# Bluepill.net
KiCad netlist of a schematic drawn in Altium Designer
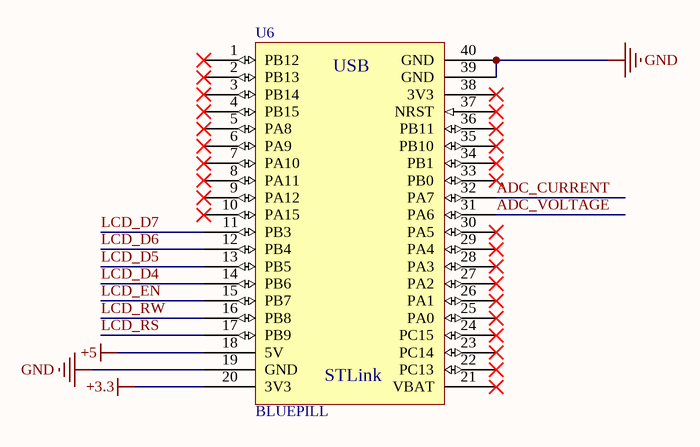
[diagram p0: Bluepill.SchDoc]

(export (version "E")
  (design (tool "Eeschema 10.0.6"))
  (components
    (comp (ref "U6")
      (value "BLUEPILL")
      (footprint "BLUEPILL")
      (description "Development board STM32F103C8T6")
      (libsource (lib "Giang's Libs") (part "BLUEPILL"))
    )
  )
  (nets
    (net (code "1") (name "+3.3") (class "Default")
      (node (ref "U6") (pin "20") (pinfunction "3V3_20") (pintype "power_in"))
    )
    (net (code "2") (name "+5") (class "Default")
      (node (ref "U6") (pin "18") (pinfunction "5V_18") (pintype "power_in"))
    )
    (net (code "3") (name "/ADC_CURRENT") (class "Default")
      (node (ref "U6") (pin "32") (pinfunction "PA7_32") (pintype "bidirectional"))
    )
    (net (code "4") (name "/ADC_VOLTAGE") (class "Default")
      (node (ref "U6") (pin "31") (pinfunction "PA6_31") (pintype "bidirectional"))
    )
    (net (code "5") (name "/LCD_D4") (class "Default")
      (node (ref "U6") (pin "14") (pinfunction "PB6_14") (pintype "bidirectional"))
    )
    (net (code "6") (name "/LCD_D5") (class "Default")
      (node (ref "U6") (pin "13") (pinfunction "PB5_13") (pintype "bidirectional"))
    )
    (net (code "7") (name "/LCD_D6") (class "Default")
      (node (ref "U6") (pin "12") (pinfunction "PB4_12") (pintype "bidirectional"))
    )
    (net (code "8") (name "/LCD_D7") (class "Default")
      (node (ref "U6") (pin "11") (pinfunction "PB3_11") (pintype "bidirectional"))
    )
    (net (code "9") (name "/LCD_EN") (class "Default")
      (node (ref "U6") (pin "15") (pinfunction "PB7_15") (pintype "bidirectional"))
    )
    (net (code "10") (name "/LCD_RS") (class "Default")
      (node (ref "U6") (pin "17") (pinfunction "PB9_17") (pintype "bidirectional"))
    )
    (net (code "11") (name "/LCD_RW") (class "Default")
      (node (ref "U6") (pin "16") (pinfunction "PB8_16") (pintype "bidirectional"))
    )
    (net (code "12") (name "GND") (class "Default")
      (node (ref "U6") (pin "19") (pinfunction "GND_19") (pintype "power_in"))
      (node (ref "U6") (pin "39") (pinfunction "GND_39") (pintype "power_in"))
      (node (ref "U6") (pin "40") (pinfunction "GND_40") (pintype "power_in"))
    )
    (net (code "13") (name "unconnected-(U6-3V3-Pad38)") (class "Default")
      (node (ref "U6") (pin "38") (pinfunction "3V3_38") (pintype "power_in+no_connect"))
    )
    (net (code "14") (name "unconnected-(U6-NRST-Pad37)") (class "Default")
      (node (ref "U6") (pin "37") (pinfunction "NRST_37") (pintype "input+no_connect"))
    )
    (net (code "15") (name "unconnected-(U6-PA0-Pad25)") (class "Default")
      (node (ref "U6") (pin "25") (pinfunction "PA0_25") (pintype "bidirectional+no_connect"))
    )
    (net (code "16") (name "unconnected-(U6-PA1-Pad26)") (class "Default")
      (node (ref "U6") (pin "26") (pinfunction "PA1_26") (pintype "bidirectional+no_connect"))
    )
    (net (code "17") (name "unconnected-(U6-PA2-Pad27)") (class "Default")
      (node (ref "U6") (pin "27") (pinfunction "PA2_27") (pintype "bidirectional+no_connect"))
    )
    (net (code "18") (name "unconnected-(U6-PA3-Pad28)") (class "Default")
      (node (ref "U6") (pin "28") (pinfunction "PA3_28") (pintype "bidirectional+no_connect"))
    )
    (net (code "19") (name "unconnected-(U6-PA4-Pad29)") (class "Default")
      (node (ref "U6") (pin "29") (pinfunction "PA4_29") (pintype "bidirectional+no_connect"))
    )
    (net (code "20") (name "unconnected-(U6-PA5-Pad30)") (class "Default")
      (node (ref "U6") (pin "30") (pinfunction "PA5_30") (pintype "bidirectional+no_connect"))
    )
    (net (code "21") (name "unconnected-(U6-PA8-Pad5)") (class "Default")
      (node (ref "U6") (pin "5") (pinfunction "PA8_5") (pintype "bidirectional+no_connect"))
    )
    (net (code "22") (name "unconnected-(U6-PA9-Pad6)") (class "Default")
      (node (ref "U6") (pin "6") (pinfunction "PA9_6") (pintype "bidirectional+no_connect"))
    )
    (net (code "23") (name "unconnected-(U6-PA10-Pad7)") (class "Default")
      (node (ref "U6") (pin "7") (pinfunction "PA10_7") (pintype "bidirectional+no_connect"))
    )
    (net (code "24") (name "unconnected-(U6-PA11-Pad8)") (class "Default")
      (node (ref "U6") (pin "8") (pinfunction "PA11_8") (pintype "bidirectional+no_connect"))
    )
    (net (code "25") (name "unconnected-(U6-PA12-Pad9)") (class "Default")
      (node (ref "U6") (pin "9") (pinfunction "PA12_9") (pintype "bidirectional+no_connect"))
    )
    (net (code "26") (name "unconnected-(U6-PA15-Pad10)") (class "Default")
      (node (ref "U6") (pin "10") (pinfunction "PA15_10") (pintype "bidirectional+no_connect"))
    )
    (net (code "27") (name "unconnected-(U6-PB0-Pad33)") (class "Default")
      (node (ref "U6") (pin "33") (pinfunction "PB0_33") (pintype "bidirectional+no_connect"))
    )
    (net (code "28") (name "unconnected-(U6-PB1-Pad34)") (class "Default")
      (node (ref "U6") (pin "34") (pinfunction "PB1_34") (pintype "bidirectional+no_connect"))
    )
    (net (code "29") (name "unconnected-(U6-PB10-Pad35)") (class "Default")
      (node (ref "U6") (pin "35") (pinfunction "PB10_35") (pintype "bidirectional+no_connect"))
    )
    (net (code "30") (name "unconnected-(U6-PB11-Pad36)") (class "Default")
      (node (ref "U6") (pin "36") (pinfunction "PB11_36") (pintype "bidirectional+no_connect"))
    )
    (net (code "31") (name "unconnected-(U6-PB12-Pad1)") (class "Default")
      (node (ref "U6") (pin "1") (pinfunction "PB12_1") (pintype "bidirectional+no_connect"))
    )
    (net (code "32") (name "unconnected-(U6-PB13-Pad2)") (class "Default")
      (node (ref "U6") (pin "2") (pinfunction "PB13_2") (pintype "bidirectional+no_connect"))
    )
    (net (code "33") (name "unconnected-(U6-PB14-Pad3)") (class "Default")
      (node (ref "U6") (pin "3") (pinfunction "PB14_3") (pintype "bidirectional+no_connect"))
    )
    (net (code "34") (name "unconnected-(U6-PB15-Pad4)") (class "Default")
      (node (ref "U6") (pin "4") (pinfunction "PB15_4") (pintype "bidirectional+no_connect"))
    )
    (net (code "35") (name "unconnected-(U6-PC13-Pad22)") (class "Default")
      (node (ref "U6") (pin "22") (pinfunction "PC13_22") (pintype "bidirectional+no_connect"))
    )
    (net (code "36") (name "unconnected-(U6-PC14-Pad23)") (class "Default")
      (node (ref "U6") (pin "23") (pinfunction "PC14_23") (pintype "bidirectional+no_connect"))
    )
    (net (code "37") (name "unconnected-(U6-PC15-Pad24)") (class "Default")
      (node (ref "U6") (pin "24") (pinfunction "PC15_24") (pintype "bidirectional+no_connect"))
    )
    (net (code "38") (name "unconnected-(U6-VBAT-Pad21)") (class "Default")
      (node (ref "U6") (pin "21") (pinfunction "VBAT_21") (pintype "power_in+no_connect"))
    )
  )
)
